# I2C_Keypad_host_module_HID.net
KiCad netlist of a schematic drawn in Altium Designer
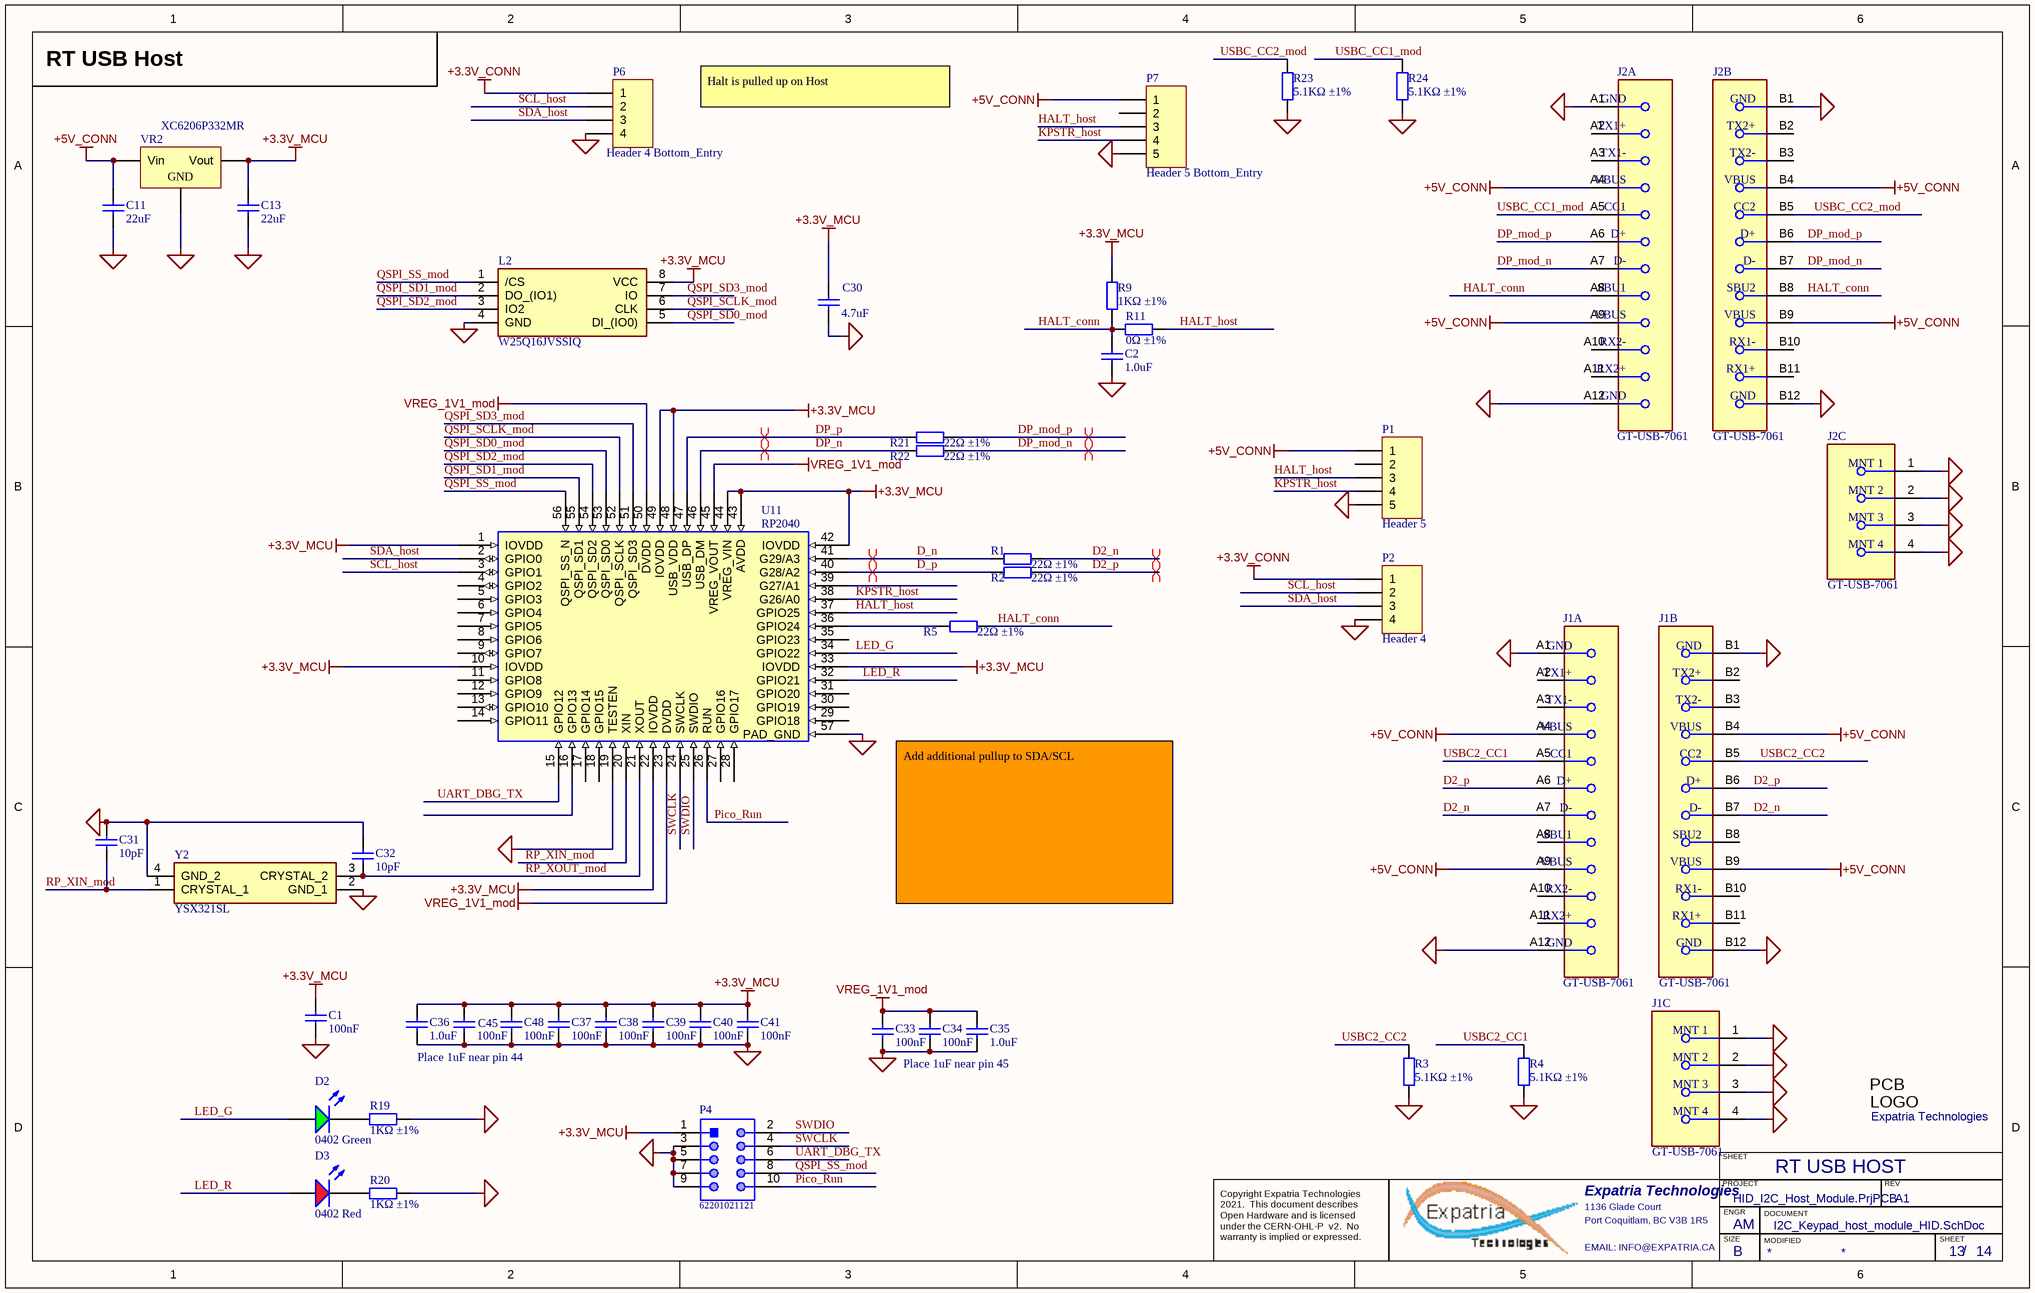
[diagram p0: I2C_Keypad_host_module_HID.SchDoc]

(export (version "E")
  (design (tool "Eeschema 10.0.6"))
  (components
    (comp (ref "C1")
      (value "100nF")
      (footprint "0402_C")
      (description "Chip capacitors")
      (fields
        (field (name "MANUFACTURER") "Samsung Electro-Mechanics")
        (field (name "PARTNUMBER") "CL05B104KO5NNNC")
      )
      (libsource (lib "Cap") (part "0402 100nF (104) 10% 16V"))
    )
    (comp (ref "C2")
      (value "1.0uF")
      (footprint "0402_C")
      (description "Chip capacitor")
      (fields
        (field (name "MANUFACTURER") "Samsung Electro-Mechanics")
        (field (name "PARTNUMBER") "CL05A105KA5NQNC")
      )
      (libsource (lib "Cap") (part "0402 1.0uF (105) 10% 25V"))
    )
    (comp (ref "C11")
      (value "22uF")
      (footprint "0603_C")
      (description "Chip capacitors")
      (fields
        (field (name "MANUFACTURER") "Samsung Electro-Mechanics")
        (field (name "PARTNUMBER") "CL10A226MQ8NRNC")
      )
      (libsource (lib "Cap") (part "0603 22uF (226) 20% 6.3V"))
    )
    (comp (ref "C13")
      (value "22uF")
      (footprint "0603_C")
      (description "Chip capacitors")
      (fields
        (field (name "MANUFACTURER") "Samsung Electro-Mechanics")
        (field (name "PARTNUMBER") "CL10A226MQ8NRNC")
      )
      (libsource (lib "Cap") (part "0603 22uF (226) 20% 6.3V"))
    )
    (comp (ref "C30")
      (value "4.7uF")
      (footprint "0402_C")
      (description "Chip capacitor")
      (fields
        (field (name "MANUFACTURER") "Samsung Electro-Mechanics")
        (field (name "PARTNUMBER") "CL05A475MP5NRNC")
      )
      (libsource (lib "Cap") (part "0402 4.7uF (475) 20% 10V"))
    )
    (comp (ref "C31")
      (value "10pF")
      (footprint "0402_C")
      (description "Chip capacitors")
      (fields
        (field (name "MANUFACTURER") "Samsung Electro-Mechanics")
        (field (name "PARTNUMBER") "CL05C100JB5NNNC")
      )
      (libsource (lib "Cap") (part "0402 10pF (100) 5% 50V"))
    )
    (comp (ref "C32")
      (value "10pF")
      (footprint "0402_C")
      (description "Chip capacitors")
      (fields
        (field (name "MANUFACTURER") "Samsung Electro-Mechanics")
        (field (name "PARTNUMBER") "CL05C100JB5NNNC")
      )
      (libsource (lib "Cap") (part "0402 10pF (100) 5% 50V"))
    )
    (comp (ref "C33")
      (value "100nF")
      (footprint "0402_C")
      (description "Chip capacitors")
      (fields
        (field (name "MANUFACTURER") "Samsung Electro-Mechanics")
        (field (name "PARTNUMBER") "CL05B104KO5NNNC")
      )
      (libsource (lib "Cap") (part "0402 100nF (104) 10% 16V"))
    )
    (comp (ref "C34")
      (value "100nF")
      (footprint "0402_C")
      (description "Chip capacitors")
      (fields
        (field (name "MANUFACTURER") "Samsung Electro-Mechanics")
        (field (name "PARTNUMBER") "CL05B104KO5NNNC")
      )
      (libsource (lib "Cap") (part "0402 100nF (104) 10% 16V"))
    )
    (comp (ref "C35")
      (value "1.0uF")
      (footprint "0402_C")
      (description "Chip capacitor")
      (fields
        (field (name "MANUFACTURER") "Samsung Electro-Mechanics")
        (field (name "PARTNUMBER") "CL05A105KA5NQNC")
      )
      (libsource (lib "Cap") (part "0402 1.0uF (105) 10% 25V"))
    )
    (comp (ref "C36")
      (value "1.0uF")
      (footprint "0402_C")
      (description "Chip capacitor")
      (fields
        (field (name "MANUFACTURER") "Samsung Electro-Mechanics")
        (field (name "PARTNUMBER") "CL05A105KA5NQNC")
      )
      (libsource (lib "Cap") (part "0402 1.0uF (105) 10% 25V"))
    )
    (comp (ref "C37")
      (value "100nF")
      (footprint "0402_C")
      (description "Chip capacitors")
      (fields
        (field (name "MANUFACTURER") "Samsung Electro-Mechanics")
        (field (name "PARTNUMBER") "CL05B104KO5NNNC")
      )
      (libsource (lib "Cap") (part "0402 100nF (104) 10% 16V"))
    )
    (comp (ref "C38")
      (value "100nF")
      (footprint "0402_C")
      (description "Chip capacitors")
      (fields
        (field (name "MANUFACTURER") "Samsung Electro-Mechanics")
        (field (name "PARTNUMBER") "CL05B104KO5NNNC")
      )
      (libsource (lib "Cap") (part "0402 100nF (104) 10% 16V"))
    )
    (comp (ref "C39")
      (value "100nF")
      (footprint "0402_C")
      (description "Chip capacitors")
      (fields
        (field (name "MANUFACTURER") "Samsung Electro-Mechanics")
        (field (name "PARTNUMBER") "CL05B104KO5NNNC")
      )
      (libsource (lib "Cap") (part "0402 100nF (104) 10% 16V"))
    )
    (comp (ref "C40")
      (value "100nF")
      (footprint "0402_C")
      (description "Chip capacitors")
      (fields
        (field (name "MANUFACTURER") "Samsung Electro-Mechanics")
        (field (name "PARTNUMBER") "CL05B104KO5NNNC")
      )
      (libsource (lib "Cap") (part "0402 100nF (104) 10% 16V"))
    )
    (comp (ref "C41")
      (value "100nF")
      (footprint "0402_C")
      (description "Chip capacitors")
      (fields
        (field (name "MANUFACTURER") "Samsung Electro-Mechanics")
        (field (name "PARTNUMBER") "CL05B104KO5NNNC")
      )
      (libsource (lib "Cap") (part "0402 100nF (104) 10% 16V"))
    )
    (comp (ref "C45")
      (value "100nF")
      (footprint "0402_C")
      (description "Chip capacitors")
      (fields
        (field (name "MANUFACTURER") "Samsung Electro-Mechanics")
        (field (name "PARTNUMBER") "CL05B104KO5NNNC")
      )
      (libsource (lib "Cap") (part "0402 100nF (104) 10% 16V"))
    )
    (comp (ref "C48")
      (value "100nF")
      (footprint "0402_C")
      (description "Chip capacitors")
      (fields
        (field (name "MANUFACTURER") "Samsung Electro-Mechanics")
        (field (name "PARTNUMBER") "CL05B104KO5NNNC")
      )
      (libsource (lib "Cap") (part "0402 100nF (104) 10% 16V"))
    )
    (comp (ref "D2")
      (value "0402 Green")
      (footprint "LED 0402_1005 RED")
      (description "LED")
      (libsource (lib "LED") (part "0402 LED Green"))
    )
    (comp (ref "D3")
      (value "0402 Red")
      (footprint "LED 0402_1005 RED")
      (description "LED")
      (libsource (lib "LED") (part "0402 LED Red"))
    )
    (comp (ref "J1")
      (value "GT-USB-7061")
      (footprint "USB-C-SMD_GT-USB-7061")
      (description "CONN RCP USB3.1 TYPEC 24P SMD VERT")
      (fields (field (name "MANUFACTURER") "G-Switch"))
      (libsource (lib "") (part "USBC-GT-USB-7061_1"))
    )
    (comp (ref "J2")
      (value "GT-USB-7061")
      (footprint "USB-C-SMD_GT-USB-7061")
      (description "CONN RCP USB3.1 TYPEC 24P SMD VERT")
      (fields (field (name "MANUFACTURER") "G-Switch"))
      (libsource (lib "I2C_Jog_Controller") (part "USBC-GT-USB-7061"))
    )
    (comp (ref "L2")
      (value "W25Q16JVSSIQ")
      (footprint "SamacSys:SOIC127P780X195-8N")
      (description "SPI NOR FLASH 16Mbit")
      (libsource (lib "*") (part "W25Q128JVSIQ_TR"))
    )
    (comp (ref "Logo1")
      (value "Expatria Technologies")
      (footprint "Expatria-Logo")
      (libsource (lib "PrintNC_GRBLHAL_Breakout") (part "SBT-Logo"))
    )
    (comp (ref "P1")
      (value "Header 5")
      (footprint "HDR1X5")
      (description "Header, 5-Pin")
      (fields (field (name "PUBLISHER") "Altium Limited"))
      (libsource (lib "PrintNC_GRBLHAL_Breakout") (part "Header 5"))
    )
    (comp (ref "P2")
      (value "Header 4")
      (footprint "HDR1X4")
      (description "Header, 4-Pin")
      (fields (field (name "PUBLISHER") "Altium Limited"))
      (libsource (lib "PrintNC_GRBLHAL_Breakout") (part "Header 4"))
    )
    (comp (ref "P4")
      (value "62201021121")
      (footprint "62201021121")
      (description "THT Vertical Pin Header WR-PHD, Pitch 1.27 mm, Dual Row, 10 pins")
      (fields (field (name "MANUFACTURER") "Wurth Elektronik") (field (name "PUBLISHER") "WurthElektronik"))
      (libsource (lib "Altium Content Vault") (part "WE-CN-2P-M-R10"))
    )
    (comp (ref "P6")
      (value "Header 4 Bottom_Entry")
      (footprint "NPTC041KFXCRC")
      (description "Header, 4-Pin")
      (fields
        (field (name "MANUFACTURER_PART_NUMBER") "NPTC041KFXCRC")
        (field (name "MANUFACTURER") "Sullins")
        (field (name "PUBLISHER") "Altium Limited")
      )
      (libsource (lib "PrintNC_GRBLHAL_Breakout") (part "Header 4"))
    )
    (comp (ref "P7")
      (value "Header 5 Bottom_Entry")
      (footprint "NPTC051KFXCRC")
      (description "Header, 5-Pin")
      (fields
        (field (name "MANUFACTURER_PART_NUMBER") "NPTC051KFXCRC")
        (field (name "MANUFACTURER") "Sullins")
      )
      (libsource (lib "PrintNC_GRBLHAL_Breakout") (part "Header 5"))
    )
    (comp (ref "R1")
      (value "22Ω ±1%")
      (footprint "0402_R")
      (description "Chip resistor")
      (fields (field (name "MANUFACTURER") "Uniroyal Elec") (field (name "PARTNUMBER") "0402WGF220JTCE"))
      (libsource (lib "RES") (part "0402 22R (22R0) 1%"))
    )
    (comp (ref "R2")
      (value "22Ω ±1%")
      (footprint "0402_R")
      (description "Chip resistor")
      (fields (field (name "MANUFACTURER") "Uniroyal Elec") (field (name "PARTNUMBER") "0402WGF220JTCE"))
      (libsource (lib "RES") (part "0402 22R (22R0) 1%"))
    )
    (comp (ref "R3")
      (value "5.1KΩ ±1%")
      (footprint "0402_R")
      (description "Chip resistor")
      (fields (field (name "MANUFACTURER") "Uniroyal Elec") (field (name "PARTNUMBER") "0402WGF5101TCE"))
      (libsource (lib "RES") (part "0402 5.1K (5101) 1%"))
    )
    (comp (ref "R4")
      (value "5.1KΩ ±1%")
      (footprint "0402_R")
      (description "Chip resistor")
      (fields (field (name "MANUFACTURER") "Uniroyal Elec") (field (name "PARTNUMBER") "0402WGF5101TCE"))
      (libsource (lib "RES") (part "0402 5.1K (5101) 1%"))
    )
    (comp (ref "R5")
      (value "22Ω ±1%")
      (footprint "0402_R")
      (description "Chip resistor")
      (fields (field (name "MANUFACTURER") "Uniroyal Elec") (field (name "PARTNUMBER") "0402WGF220JTCE"))
      (libsource (lib "RES") (part "0402 22R (22R0) 1%"))
    )
    (comp (ref "R9")
      (value "1KΩ ±1%")
      (footprint "0402_R")
      (description "Chip resistor")
      (fields (field (name "MANUFACTURER") "Uniroyal Elec") (field (name "PARTNUMBER") "0402WGF1001TCE"))
      (libsource (lib "") (part "0402 1K (1001) 1%_1"))
    )
    (comp (ref "R11")
      (value "0Ω ±1%")
      (footprint "0402_R")
      (description "Chip resistor")
      (fields (field (name "POWER") "1/16W") (field (name "MANUFACTURER") "Uniroyal Elec"))
      (libsource (lib "RES") (part "0402 0R (0R0) 1%"))
    )
    (comp (ref "R19")
      (value "1KΩ ±1%")
      (footprint "0402_R")
      (description "Chip resistor")
      (fields (field (name "MANUFACTURER") "Uniroyal Elec") (field (name "PARTNUMBER") "0402WGF1001TCE"))
      (libsource (lib "RES") (part "0402 1K (1001) 1%"))
    )
    (comp (ref "R20")
      (value "1KΩ ±1%")
      (footprint "0402_R")
      (description "Chip resistor")
      (fields (field (name "MANUFACTURER") "Uniroyal Elec") (field (name "PARTNUMBER") "0402WGF1001TCE"))
      (libsource (lib "RES") (part "0402 1K (1001) 1%"))
    )
    (comp (ref "R21")
      (value "22Ω ±1%")
      (footprint "0402_R")
      (description "Chip resistor")
      (fields (field (name "MANUFACTURER") "Uniroyal Elec") (field (name "PARTNUMBER") "0402WGF220JTCE"))
      (libsource (lib "RES") (part "0402 22R (22R0) 1%"))
    )
    (comp (ref "R22")
      (value "22Ω ±1%")
      (footprint "0402_R")
      (description "Chip resistor")
      (fields (field (name "MANUFACTURER") "Uniroyal Elec") (field (name "PARTNUMBER") "0402WGF220JTCE"))
      (libsource (lib "RES") (part "0402 22R (22R0) 1%"))
    )
    (comp (ref "R23")
      (value "5.1KΩ ±1%")
      (footprint "0402_R")
      (description "Chip resistor")
      (fields (field (name "MANUFACTURER") "Uniroyal Elec") (field (name "PARTNUMBER") "0402WGF5101TCE"))
      (libsource (lib "RES") (part "0402 5.1K (5101) 1%"))
    )
    (comp (ref "R24")
      (value "5.1KΩ ±1%")
      (footprint "0402_R")
      (description "Chip resistor")
      (fields (field (name "MANUFACTURER") "Uniroyal Elec") (field (name "PARTNUMBER") "0402WGF5101TCE"))
      (libsource (lib "RES") (part "0402 5.1K (5101) 1%"))
    )
    (comp (ref "U11")
      (value "RP2040")
      (footprint "RP2040")
      (description "RP2040 First MCU from RPI")
      (libsource (lib "Universal_CNC_Breakout") (part "RP2040"))
    )
    (comp (ref "VR2")
      (value "XC6206P332MR")
      (footprint "SOT-23-3L")
      (description "200mA 680mV@(100mA) Fixed 3.3V~3.3V Positive 1 6V SOT-23-3L Linear Voltage Regulators (LDO) ROHS")
      (libsource (lib "LDO") (part "SOT-23 XC6206P332MR"))
    )
    (comp (ref "Y2")
      (value "YSX321SL")
      (footprint "SamacSys:YSX321SL")
      (description "Crystal or Oscillator")
      (libsource (lib "*") (part "YSX321SL"))
    )
  )
  (nets
    (net (code "1") (name "+3.3V_CONN") (class "Default")
      (node (ref "P2") (pin "1") (pinfunction "1_1") (pintype "passive"))
      (node (ref "P6") (pin "1") (pinfunction "1_1") (pintype "passive"))
    )
    (net (code "2") (name "+3.3V_MCU") (class "Default")
      (node (ref "C1") (pin "2") (pinfunction "2_2") (pintype "passive"))
      (node (ref "C13") (pin "2") (pinfunction "2_2") (pintype "passive"))
      (node (ref "C30") (pin "2") (pinfunction "2_2") (pintype "passive"))
      (node (ref "C36") (pin "2") (pinfunction "2_2") (pintype "passive"))
      (node (ref "C37") (pin "2") (pinfunction "2_2") (pintype "passive"))
      (node (ref "C38") (pin "2") (pinfunction "2_2") (pintype "passive"))
      (node (ref "C39") (pin "2") (pinfunction "2_2") (pintype "passive"))
      (node (ref "C40") (pin "2") (pinfunction "2_2") (pintype "passive"))
      (node (ref "C41") (pin "2") (pinfunction "2_2") (pintype "passive"))
      (node (ref "C45") (pin "2") (pinfunction "2_2") (pintype "passive"))
      (node (ref "C48") (pin "2") (pinfunction "2_2") (pintype "passive"))
      (node (ref "L2") (pin "8") (pinfunction "VCC_8") (pintype "passive"))
      (node (ref "P4") (pin "1") (pinfunction "1_1") (pintype "passive"))
      (node (ref "R9") (pin "2") (pinfunction "2_2") (pintype "passive"))
      (node (ref "U11") (pin "1") (pinfunction "IOVDD_1") (pintype "input"))
      (node (ref "U11") (pin "10") (pinfunction "IOVDD_10") (pintype "input"))
      (node (ref "U11") (pin "22") (pinfunction "IOVDD_22") (pintype "input"))
      (node (ref "U11") (pin "33") (pinfunction "IOVDD_33") (pintype "input"))
      (node (ref "U11") (pin "42") (pinfunction "IOVDD_42") (pintype "input"))
      (node (ref "U11") (pin "43") (pinfunction "AVDD_43") (pintype "input"))
      (node (ref "U11") (pin "44") (pinfunction "VREG_VIN_44") (pintype "input"))
      (node (ref "U11") (pin "48") (pinfunction "USB_VDD_48") (pintype "input"))
      (node (ref "U11") (pin "49") (pinfunction "IOVDD_49") (pintype "input"))
      (node (ref "VR2") (pin "2") (pinfunction "Vout_2") (pintype "passive"))
    )
    (net (code "3") (name "+5V_CONN") (class "Default")
      (node (ref "C11") (pin "2") (pinfunction "2_2") (pintype "passive"))
      (node (ref "J1") (pin "A4") (pinfunction "VBUS_A4") (pintype "passive"))
      (node (ref "J1") (pin "A9") (pinfunction "VBUS_A9") (pintype "passive"))
      (node (ref "J1") (pin "B4") (pinfunction "VBUS_B4") (pintype "passive"))
      (node (ref "J1") (pin "B9") (pinfunction "VBUS_B9") (pintype "passive"))
      (node (ref "J2") (pin "A4") (pinfunction "VBUS_A4") (pintype "passive"))
      (node (ref "J2") (pin "A9") (pinfunction "VBUS_A9") (pintype "passive"))
      (node (ref "J2") (pin "B4") (pinfunction "VBUS_B4") (pintype "passive"))
      (node (ref "J2") (pin "B9") (pinfunction "VBUS_B9") (pintype "passive"))
      (node (ref "P1") (pin "1") (pinfunction "1_1") (pintype "passive"))
      (node (ref "P7") (pin "1") (pinfunction "1_1") (pintype "passive"))
      (node (ref "VR2") (pin "3") (pinfunction "Vin_3") (pintype "passive"))
    )
    (net (code "4") (name "/D2_n") (class "Default")
      (node (ref "J1") (pin "A7") (pinfunction "D-_A7") (pintype "passive"))
      (node (ref "J1") (pin "B7") (pinfunction "D-_B7") (pintype "passive"))
      (node (ref "R1") (pin "1") (pinfunction "1_1") (pintype "passive"))
    )
    (net (code "5") (name "/D2_p") (class "Default")
      (node (ref "J1") (pin "A6") (pinfunction "D+_A6") (pintype "passive"))
      (node (ref "J1") (pin "B6") (pinfunction "D+_B6") (pintype "passive"))
      (node (ref "R2") (pin "1") (pinfunction "1_1") (pintype "passive"))
    )
    (net (code "6") (name "/DP_mod_n") (class "Default")
      (node (ref "J2") (pin "A7") (pinfunction "D-_A7") (pintype "passive"))
      (node (ref "J2") (pin "B7") (pinfunction "D-_B7") (pintype "passive"))
      (node (ref "R22") (pin "1") (pinfunction "1_1") (pintype "passive"))
    )
    (net (code "7") (name "/DP_mod_p") (class "Default")
      (node (ref "J2") (pin "A6") (pinfunction "D+_A6") (pintype "passive"))
      (node (ref "J2") (pin "B6") (pinfunction "D+_B6") (pintype "passive"))
      (node (ref "R21") (pin "1") (pinfunction "1_1") (pintype "passive"))
    )
    (net (code "8") (name "/DP_n") (class "Default")
      (node (ref "R22") (pin "2") (pinfunction "2_2") (pintype "passive"))
      (node (ref "U11") (pin "46") (pinfunction "USB_DM_46") (pintype "input"))
    )
    (net (code "9") (name "/DP_p") (class "Default")
      (node (ref "R21") (pin "2") (pinfunction "2_2") (pintype "passive"))
      (node (ref "U11") (pin "47") (pinfunction "USB_DP_47") (pintype "input"))
    )
    (net (code "10") (name "/D_n") (class "Default")
      (node (ref "R1") (pin "2") (pinfunction "2_2") (pintype "passive"))
      (node (ref "U11") (pin "41") (pinfunction "G29/A3_41") (pintype "input"))
    )
    (net (code "11") (name "/D_p") (class "Default")
      (node (ref "R2") (pin "2") (pinfunction "2_2") (pintype "passive"))
      (node (ref "U11") (pin "40") (pinfunction "G28/A2_40") (pintype "input"))
    )
    (net (code "12") (name "/HALT_conn") (class "Default")
      (node (ref "C2") (pin "2") (pinfunction "2_2") (pintype "passive"))
      (node (ref "J2") (pin "A8") (pinfunction "SBU1_A8") (pintype "passive"))
      (node (ref "J2") (pin "B8") (pinfunction "SBU2_B8") (pintype "passive"))
      (node (ref "R11") (pin "1") (pinfunction "1_1") (pintype "passive"))
      (node (ref "R5") (pin "1") (pinfunction "1_1") (pintype "passive"))
      (node (ref "R9") (pin "1") (pinfunction "1_1") (pintype "passive"))
    )
    (net (code "13") (name "/HALT_host") (class "Default")
      (node (ref "P1") (pin "3") (pinfunction "3_3") (pintype "passive"))
      (node (ref "P7") (pin "3") (pinfunction "3_3") (pintype "passive"))
      (node (ref "R11") (pin "2") (pinfunction "2_2") (pintype "passive"))
      (node (ref "U11") (pin "37") (pinfunction "GPIO25_37") (pintype "input"))
    )
    (net (code "14") (name "/KPSTR_host") (class "Default")
      (node (ref "P1") (pin "4") (pinfunction "4_4") (pintype "passive"))
      (node (ref "P7") (pin "4") (pinfunction "4_4") (pintype "passive"))
      (node (ref "U11") (pin "38") (pinfunction "G26/A0_38") (pintype "input"))
    )
    (net (code "15") (name "/LED_G") (class "Default")
      (node (ref "D2") (pin "A") (pinfunction "A_A") (pintype "passive"))
      (node (ref "U11") (pin "34") (pinfunction "GPIO22_34") (pintype "input"))
    )
    (net (code "16") (name "/LED_R") (class "Default")
      (node (ref "D3") (pin "A") (pinfunction "A_A") (pintype "passive"))
      (node (ref "U11") (pin "32") (pinfunction "GPIO21_32") (pintype "input"))
    )
    (net (code "17") (name "/Pico_Run") (class "Default")
      (node (ref "P4") (pin "10") (pinfunction "10_10") (pintype "passive"))
      (node (ref "U11") (pin "26") (pinfunction "RUN_26") (pintype "input"))
    )
    (net (code "18") (name "/QSPI_SCLK_mod") (class "Default")
      (node (ref "L2") (pin "6") (pinfunction "CLK_6") (pintype "passive"))
      (node (ref "U11") (pin "52") (pinfunction "QSPI_SCLK_52") (pintype "input"))
    )
    (net (code "19") (name "/QSPI_SD0_mod") (class "Default")
      (node (ref "L2") (pin "5") (pinfunction "DI_(IO0)_5") (pintype "passive"))
      (node (ref "U11") (pin "53") (pinfunction "QSPI_SD0_53") (pintype "input"))
    )
    (net (code "20") (name "/QSPI_SD1_mod") (class "Default")
      (node (ref "L2") (pin "2") (pinfunction "DO_(IO1)_2") (pintype "passive"))
      (node (ref "U11") (pin "55") (pinfunction "QSPI_SD1_55") (pintype "input"))
    )
    (net (code "21") (name "/QSPI_SD2_mod") (class "Default")
      (node (ref "L2") (pin "3") (pinfunction "IO2_3") (pintype "passive"))
      (node (ref "U11") (pin "54") (pinfunction "QSPI_SD2_54") (pintype "input"))
    )
    (net (code "22") (name "/QSPI_SD3_mod") (class "Default")
      (node (ref "L2") (pin "7") (pinfunction "IO_7") (pintype "passive"))
      (node (ref "U11") (pin "51") (pinfunction "QSPI_SD3_51") (pintype "input"))
    )
    (net (code "23") (name "/QSPI_SS_mod") (class "Default")
      (node (ref "L2") (pin "1") (pinfunction "/CS_1") (pintype "passive"))
      (node (ref "P4") (pin "8") (pinfunction "8_8") (pintype "passive"))
      (node (ref "U11") (pin "56") (pinfunction "QSPI_SS_N_56") (pintype "input"))
    )
    (net (code "24") (name "/RP_XIN_mod") (class "Default")
      (node (ref "C31") (pin "1") (pinfunction "1_1") (pintype "passive"))
      (node (ref "U11") (pin "20") (pinfunction "XIN_20") (pintype "input"))
      (node (ref "Y2") (pin "1") (pinfunction "CRYSTAL_1_1") (pintype "passive"))
    )
    (net (code "25") (name "/RP_XOUT_mod") (class "Default")
      (node (ref "C32") (pin "1") (pinfunction "1_1") (pintype "passive"))
      (node (ref "U11") (pin "21") (pinfunction "XOUT_21") (pintype "input"))
      (node (ref "Y2") (pin "3") (pinfunction "CRYSTAL_2_3") (pintype "passive"))
    )
    (net (code "26") (name "/SCL_host") (class "Default")
      (node (ref "P2") (pin "2") (pinfunction "2_2") (pintype "passive"))
      (node (ref "P6") (pin "2") (pinfunction "2_2") (pintype "passive"))
      (node (ref "U11") (pin "3") (pinfunction "GPIO1_3") (pintype "bidirectional"))
    )
    (net (code "27") (name "/SDA_host") (class "Default")
      (node (ref "P2") (pin "3") (pinfunction "3_3") (pintype "passive"))
      (node (ref "P6") (pin "3") (pinfunction "3_3") (pintype "passive"))
      (node (ref "U11") (pin "2") (pinfunction "GPIO0_2") (pintype "bidirectional"))
    )
    (net (code "28") (name "/SWCLK") (class "Default")
      (node (ref "P4") (pin "4") (pinfunction "4_4") (pintype "passive"))
      (node (ref "U11") (pin "24") (pinfunction "SWCLK_24") (pintype "input"))
    )
    (net (code "29") (name "/SWDIO") (class "Default")
      (node (ref "P4") (pin "2") (pinfunction "2_2") (pintype "passive"))
      (node (ref "U11") (pin "25") (pinfunction "SWDIO_25") (pintype "input"))
    )
    (net (code "30") (name "/UART_DBG_TX") (class "Default")
      (node (ref "P4") (pin "6") (pinfunction "6_6") (pintype "passive"))
      (node (ref "U11") (pin "15") (pinfunction "GPIO12_15") (pintype "input"))
    )
    (net (code "31") (name "/USBC2_CC1") (class "Default")
      (node (ref "J1") (pin "A5") (pinfunction "CC1_A5") (pintype "passive"))
      (node (ref "R4") (pin "1") (pinfunction "1_1") (pintype "passive"))
    )
    (net (code "32") (name "/USBC2_CC2") (class "Default")
      (node (ref "J1") (pin "B5") (pinfunction "CC2_B5") (pintype "passive"))
      (node (ref "R3") (pin "1") (pinfunction "1_1") (pintype "passive"))
    )
    (net (code "33") (name "/USBC_CC1_mod") (class "Default")
      (node (ref "J2") (pin "A5") (pinfunction "CC1_A5") (pintype "passive"))
      (node (ref "R24") (pin "1") (pinfunction "1_1") (pintype "passive"))
    )
    (net (code "34") (name "/USBC_CC2_mod") (class "Default")
      (node (ref "J2") (pin "B5") (pinfunction "CC2_B5") (pintype "passive"))
      (node (ref "R23") (pin "1") (pinfunction "1_1") (pintype "passive"))
    )
    (net (code "35") (name "GND") (class "Default")
      (node (ref "C1") (pin "1") (pinfunction "1_1") (pintype "passive"))
      (node (ref "C11") (pin "1") (pinfunction "1_1") (pintype "passive"))
      (node (ref "C13") (pin "1") (pinfunction "1_1") (pintype "passive"))
      (node (ref "C2") (pin "1") (pinfunction "1_1") (pintype "passive"))
      (node (ref "C30") (pin "1") (pinfunction "1_1") (pintype "passive"))
      (node (ref "C31") (pin "2") (pinfunction "2_2") (pintype "passive"))
      (node (ref "C32") (pin "2") (pinfunction "2_2") (pintype "passive"))
      (node (ref "C33") (pin "1") (pinfunction "1_1") (pintype "passive"))
      (node (ref "C34") (pin "1") (pinfunction "1_1") (pintype "passive"))
      (node (ref "C35") (pin "1") (pinfunction "1_1") (pintype "passive"))
      (node (ref "C36") (pin "1") (pinfunction "1_1") (pintype "passive"))
      (node (ref "C37") (pin "1") (pinfunction "1_1") (pintype "passive"))
      (node (ref "C38") (pin "1") (pinfunction "1_1") (pintype "passive"))
      (node (ref "C39") (pin "1") (pinfunction "1_1") (pintype "passive"))
      (node (ref "C40") (pin "1") (pinfunction "1_1") (pintype "passive"))
      (node (ref "C41") (pin "1") (pinfunction "1_1") (pintype "passive"))
      (node (ref "C45") (pin "1") (pinfunction "1_1") (pintype "passive"))
      (node (ref "C48") (pin "1") (pinfunction "1_1") (pintype "passive"))
      (node (ref "J1") (pin "1") (pinfunction "MNT_1_1") (pintype "passive"))
      (node (ref "J1") (pin "2") (pinfunction "MNT_2_2") (pintype "passive"))
      (node (ref "J1") (pin "3") (pinfunction "MNT_3_3") (pintype "passive"))
      (node (ref "J1") (pin "4") (pinfunction "MNT_4_4") (pintype "passive"))
      (node (ref "J1") (pin "A1") (pinfunction "GND_A1") (pintype "passive"))
      (node (ref "J1") (pin "A12") (pinfunction "GND_A12") (pintype "passive"))
      (node (ref "J1") (pin "B1") (pinfunction "GND_B1") (pintype "passive"))
      (node (ref "J1") (pin "B12") (pinfunction "GND_B12") (pintype "passive"))
      (node (ref "J2") (pin "1") (pinfunction "MNT_1_1") (pintype "passive"))
      (node (ref "J2") (pin "2") (pinfunction "MNT_2_2") (pintype "passive"))
      (node (ref "J2") (pin "3") (pinfunction "MNT_3_3") (pintype "passive"))
      (node (ref "J2") (pin "4") (pinfunction "MNT_4_4") (pintype "passive"))
      (node (ref "J2") (pin "A1") (pinfunction "GND_A1") (pintype "passive"))
      (node (ref "J2") (pin "A12") (pinfunction "GND_A12") (pintype "passive"))
      (node (ref "J2") (pin "B1") (pinfunction "GND_B1") (pintype "passive"))
      (node (ref "J2") (pin "B12") (pinfunction "GND_B12") (pintype "passive"))
      (node (ref "L2") (pin "4") (pinfunction "GND_4") (pintype "passive"))
      (node (ref "P1") (pin "5") (pinfunction "5_5") (pintype "passive"))
      (node (ref "P2") (pin "4") (pinfunction "4_4") (pintype "passive"))
      (node (ref "P4") (pin "3") (pinfunction "3_3") (pintype "passive"))
      (node (ref "P4") (pin "5") (pinfunction "5_5") (pintype "passive"))
      (node (ref "P4") (pin "7") (pinfunction "7_7") (pintype "passive"))
      (node (ref "P4") (pin "9") (pinfunction "9_9") (pintype "passive"))
      (node (ref "P6") (pin "4") (pinfunction "4_4") (pintype "passive"))
      (node (ref "P7") (pin "5") (pinfunction "5_5") (pintype "passive"))
      (node (ref "R19") (pin "2") (pinfunction "2_2") (pintype "passive"))
      (node (ref "R20") (pin "2") (pinfunction "2_2") (pintype "passive"))
      (node (ref "R23") (pin "2") (pinfunction "2_2") (pintype "passive"))
      (node (ref "R24") (pin "2") (pinfunction "2_2") (pintype "passive"))
      (node (ref "R3") (pin "2") (pinfunction "2_2") (pintype "passive"))
      (node (ref "R4") (pin "2") (pinfunction "2_2") (pintype "passive"))
      (node (ref "U11") (pin "19") (pinfunction "TESTEN_19") (pintype "input"))
      (node (ref "U11") (pin "57") (pinfunction "PAD_GND_57") (pintype "input"))
      (node (ref "VR2") (pin "1") (pinfunction "GND_1") (pintype "passive"))
      (node (ref "Y2") (pin "2") (pinfunction "GND_1_2") (pintype "passive"))
      (node (ref "Y2") (pin "4") (pinfunction "GND_2_4") (pintype "passive"))
    )
    (net (code "36") (name "Net-(D2-PadK)") (class "Default")
      (node (ref "D2") (pin "K") (pinfunction "K_K") (pintype "passive"))
      (node (ref "R19") (pin "1") (pinfunction "1_1") (pintype "passive"))
    )
    (net (code "37") (name "Net-(D3-PadK)") (class "Default")
      (node (ref "D3") (pin "K") (pinfunction "K_K") (pintype "passive"))
      (node (ref "R20") (pin "1") (pinfunction "1_1") (pintype "passive"))
    )
    (net (code "38") (name "Net-(U11-GPIO24)") (class "Default")
      (node (ref "R5") (pin "2") (pinfunction "2_2") (pintype "passive"))
      (node (ref "U11") (pin "36") (pinfunction "GPIO24_36") (pintype "input"))
    )
    (net (code "39") (name "VREG_1V1_mod") (class "Default")
      (node (ref "C33") (pin "2") (pinfunction "2_2") (pintype "passive"))
      (node (ref "C34") (pin "2") (pinfunction "2_2") (pintype "passive"))
      (node (ref "C35") (pin "2") (pinfunction "2_2") (pintype "passive"))
      (node (ref "U11") (pin "23") (pinfunction "DVDD_23") (pintype "input"))
      (node (ref "U11") (pin "45") (pinfunction "VREG_VOUT_45") (pintype "input"))
      (node (ref "U11") (pin "50") (pinfunction "DVDD_50") (pintype "input"))
    )
    (net (code "40") (name "unconnected-(J1A-RX2+-PadA11)") (class "Default")
      (node (ref "J1") (pin "A11") (pinfunction "RX2+_A11") (pintype "passive"))
    )
    (net (code "41") (name "unconnected-(J1A-RX2--PadA10)") (class "Default")
      (node (ref "J1") (pin "A10") (pinfunction "RX2-_A10") (pintype "passive"))
    )
    (net (code "42") (name "unconnected-(J1A-SBU1-PadA8)") (class "Default")
      (node (ref "J1") (pin "A8") (pinfunction "SBU1_A8") (pintype "passive"))
    )
    (net (code "43") (name "unconnected-(J1A-TX1+-PadA2)") (class "Default")
      (node (ref "J1") (pin "A2") (pinfunction "TX1+_A2") (pintype "passive"))
    )
    (net (code "44") (name "unconnected-(J1A-TX1--PadA3)") (class "Default")
      (node (ref "J1") (pin "A3") (pinfunction "TX1-_A3") (pintype "passive"))
    )
    (net (code "45") (name "unconnected-(J1B-RX1+-PadB11)") (class "Default")
      (node (ref "J1") (pin "B11") (pinfunction "RX1+_B11") (pintype "passive"))
    )
    (net (code "46") (name "unconnected-(J1B-RX1--PadB10)") (class "Default")
      (node (ref "J1") (pin "B10") (pinfunction "RX1-_B10") (pintype "passive"))
    )
    (net (code "47") (name "unconnected-(J1B-SBU2-PadB8)") (class "Default")
      (node (ref "J1") (pin "B8") (pinfunction "SBU2_B8") (pintype "passive"))
    )
    (net (code "48") (name "unconnected-(J1B-TX2+-PadB2)") (class "Default")
      (node (ref "J1") (pin "B2") (pinfunction "TX2+_B2") (pintype "passive"))
    )
    (net (code "49") (name "unconnected-(J1B-TX2--PadB3)") (class "Default")
      (node (ref "J1") (pin "B3") (pinfunction "TX2-_B3") (pintype "passive"))
    )
    (net (code "50") (name "unconnected-(J2A-RX2+-PadA11)") (class "Default")
      (node (ref "J2") (pin "A11") (pinfunction "RX2+_A11") (pintype "passive"))
    )
    (net (code "51") (name "unconnected-(J2A-RX2--PadA10)") (class "Default")
      (node (ref "J2") (pin "A10") (pinfunction "RX2-_A10") (pintype "passive"))
    )
    (net (code "52") (name "unconnected-(J2A-TX1+-PadA2)") (class "Default")
      (node (ref "J2") (pin "A2") (pinfunction "TX1+_A2") (pintype "passive"))
    )
    (net (code "53") (name "unconnected-(J2A-TX1--PadA3)") (class "Default")
      (node (ref "J2") (pin "A3") (pinfunction "TX1-_A3") (pintype "passive"))
    )
    (net (code "54") (name "unconnected-(J2B-RX1+-PadB11)") (class "Default")
      (node (ref "J2") (pin "B11") (pinfunction "RX1+_B11") (pintype "passive"))
    )
    (net (code "55") (name "unconnected-(J2B-RX1--PadB10)") (class "Default")
      (node (ref "J2") (pin "B10") (pinfunction "RX1-_B10") (pintype "passive"))
    )
    (net (code "56") (name "unconnected-(J2B-TX2+-PadB2)") (class "Default")
      (node (ref "J2") (pin "B2") (pinfunction "TX2+_B2") (pintype "passive"))
    )
    (net (code "57") (name "unconnected-(J2B-TX2--PadB3)") (class "Default")
      (node (ref "J2") (pin "B3") (pinfunction "TX2-_B3") (pintype "passive"))
    )
    (net (code "58") (name "unconnected-(P1-Pad2)") (class "Default")
      (node (ref "P1") (pin "2") (pinfunction "2_2") (pintype "passive"))
    )
    (net (code "59") (name "unconnected-(P7-Pad2)") (class "Default")
      (node (ref "P7") (pin "2") (pinfunction "2_2") (pintype "passive"))
    )
    (net (code "60") (name "unconnected-(U11-G27{slash}A1-Pad39)") (class "Default")
      (node (ref "U11") (pin "39") (pinfunction "G27/A1_39") (pintype "input"))
    )
    (net (code "61") (name "unconnected-(U11-GPIO2-Pad4)") (class "Default")
      (node (ref "U11") (pin "4") (pinfunction "GPIO2_4") (pintype "bidirectional"))
    )
    (net (code "62") (name "unconnected-(U11-GPIO3-Pad5)") (class "Default")
      (node (ref "U11") (pin "5") (pinfunction "GPIO3_5") (pintype "input"))
    )
    (net (code "63") (name "unconnected-(U11-GPIO4-Pad6)") (class "Default")
      (node (ref "U11") (pin "6") (pinfunction "GPIO4_6") (pintype "input"))
    )
    (net (code "64") (name "unconnected-(U11-GPIO5-Pad7)") (class "Default")
      (node (ref "U11") (pin "7") (pinfunction "GPIO5_7") (pintype "input"))
    )
    (net (code "65") (name "unconnected-(U11-GPIO6-Pad8)") (class "Default")
      (node (ref "U11") (pin "8") (pinfunction "GPIO6_8") (pintype "input"))
    )
    (net (code "66") (name "unconnected-(U11-GPIO7-Pad9)") (class "Default")
      (node (ref "U11") (pin "9") (pinfunction "GPIO7_9") (pintype "bidirectional"))
    )
    (net (code "67") (name "unconnected-(U11-GPIO8-Pad11)") (class "Default")
      (node (ref "U11") (pin "11") (pinfunction "GPIO8_11") (pintype "input"))
    )
    (net (code "68") (name "unconnected-(U11-GPIO9-Pad12)") (class "Default")
      (node (ref "U11") (pin "12") (pinfunction "GPIO9_12") (pintype "input"))
    )
    (net (code "69") (name "unconnected-(U11-GPIO10-Pad13)") (class "Default")
      (node (ref "U11") (pin "13") (pinfunction "GPIO10_13") (pintype "bidirectional"))
    )
    (net (code "70") (name "unconnected-(U11-GPIO11-Pad14)") (class "Default")
      (node (ref "U11") (pin "14") (pinfunction "GPIO11_14") (pintype "input"))
    )
    (net (code "71") (name "unconnected-(U11-GPIO13-Pad16)") (class "Default")
      (node (ref "U11") (pin "16") (pinfunction "GPIO13_16") (pintype "input"))
    )
    (net (code "72") (name "unconnected-(U11-GPIO14-Pad17)") (class "Default")
      (node (ref "U11") (pin "17") (pinfunction "GPIO14_17") (pintype "input"))
    )
    (net (code "73") (name "unconnected-(U11-GPIO15-Pad18)") (class "Default")
      (node (ref "U11") (pin "18") (pinfunction "GPIO15_18") (pintype "input"))
    )
    (net (code "74") (name "unconnected-(U11-GPIO16-Pad27)") (class "Default")
      (node (ref "U11") (pin "27") (pinfunction "GPIO16_27") (pintype "input"))
    )
    (net (code "75") (name "unconnected-(U11-GPIO17-Pad28)") (class "Default")
      (node (ref "U11") (pin "28") (pinfunction "GPIO17_28") (pintype "input"))
    )
    (net (code "76") (name "unconnected-(U11-GPIO18-Pad29)") (class "Default")
      (node (ref "U11") (pin "29") (pinfunction "GPIO18_29") (pintype "input"))
    )
    (net (code "77") (name "unconnected-(U11-GPIO19-Pad30)") (class "Default")
      (node (ref "U11") (pin "30") (pinfunction "GPIO19_30") (pintype "input"))
    )
    (net (code "78") (name "unconnected-(U11-GPIO20-Pad31)") (class "Default")
      (node (ref "U11") (pin "31") (pinfunction "GPIO20_31") (pintype "input"))
    )
    (net (code "79") (name "unconnected-(U11-GPIO23-Pad35)") (class "Default")
      (node (ref "U11") (pin "35") (pinfunction "GPIO23_35") (pintype "input"))
    )
  )
)
